# Sapflux-Basic_AltB.net
KiCad netlist of a schematic drawn in EAGLE
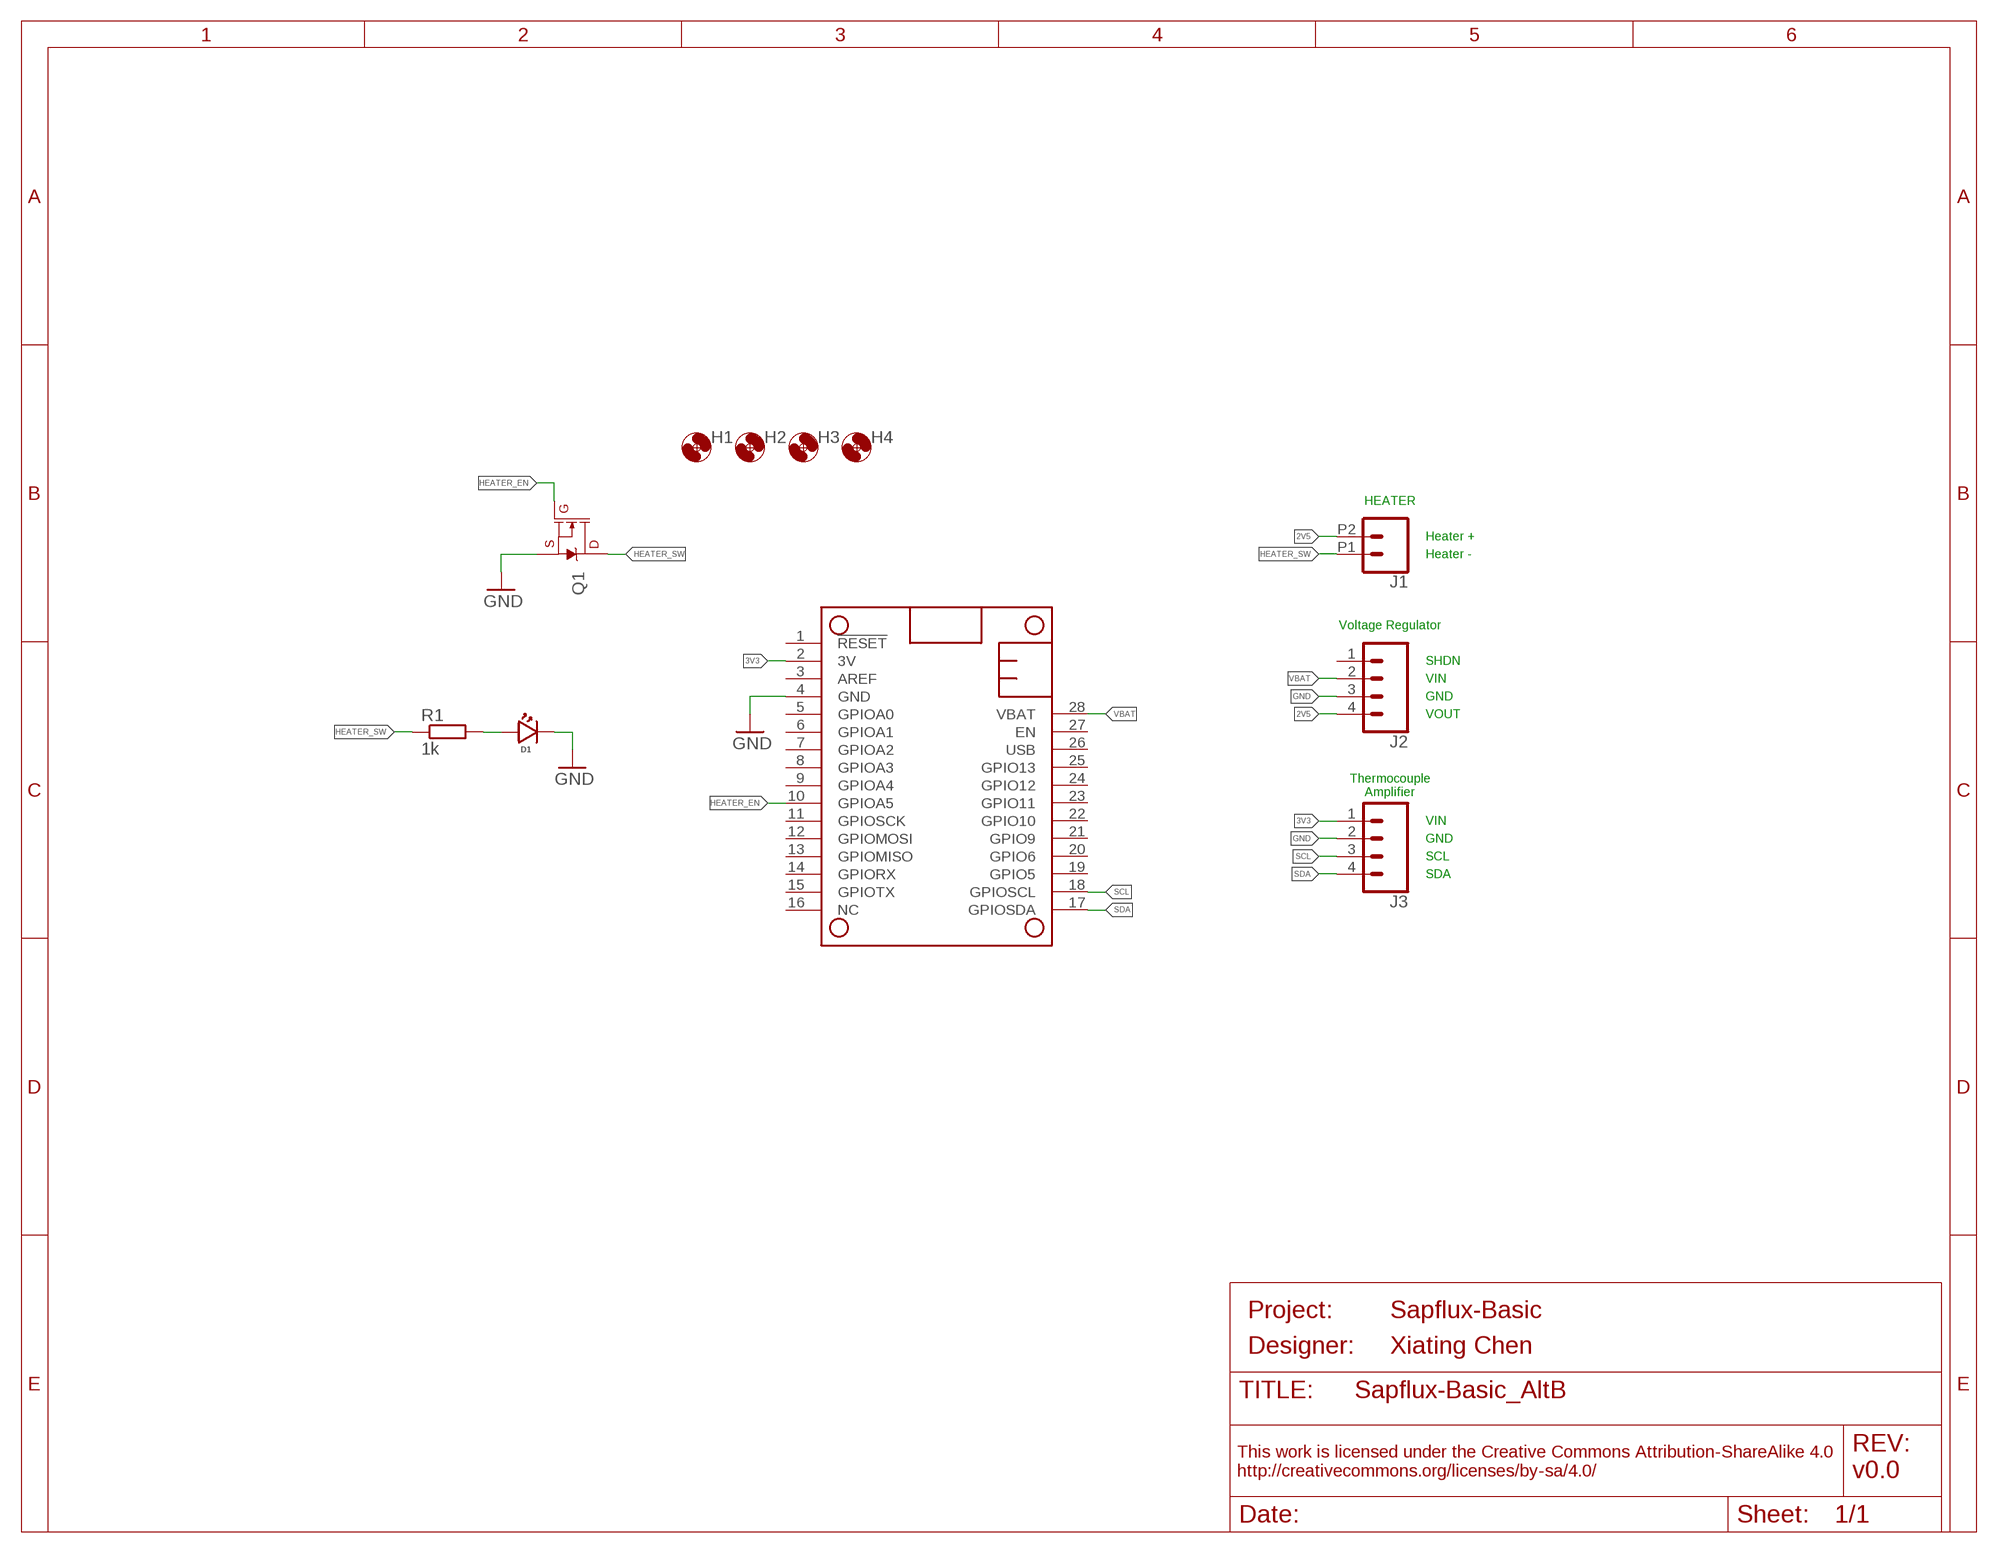
[diagram p0: schematic, sheet 1]

(export (version "E")
  (design (tool "Eeschema 10.0.6"))
  (components
    (comp (ref "D1")
      (value "LED3MM")
      (footprint "eagle-import:LED_3MM")
      (libsource (lib "eagle-import") (part "LED3MM"))
    )
    (comp (ref "H1")
      (value "MOUNTING_HOLE4_NP")
      (footprint "eagle-import:4_40")
      (fields (field (name "MPN") "DNP"))
      (libsource (lib "eagle-import") (part "MOUNTING_HOLE4_NP"))
    )
    (comp (ref "H2")
      (value "MOUNTING_HOLE4_NP")
      (footprint "eagle-import:4_40")
      (fields (field (name "MPN") "DNP"))
      (libsource (lib "eagle-import") (part "MOUNTING_HOLE4_NP"))
    )
    (comp (ref "H3")
      (value "MOUNTING_HOLE4_NP")
      (footprint "eagle-import:4_40")
      (fields (field (name "MPN") "DNP"))
      (libsource (lib "eagle-import") (part "MOUNTING_HOLE4_NP"))
    )
    (comp (ref "H4")
      (value "MOUNTING_HOLE4_NP")
      (footprint "eagle-import:4_40")
      (fields (field (name "MPN") "DNP"))
      (libsource (lib "eagle-import") (part "MOUNTING_HOLE4_NP"))
    )
    (comp (ref "J1")
      (value "CONN_2")
      (footprint "eagle-import:1X02_2.54_SCREWTERM_ROUND")
      (fields (field (name "MF") "OnShore") (field (name "MPN") "OSTVN02A150"))
      (libsource (lib "eagle-import") (part "CONN_022.54_SCREW_ROUND"))
    )
    (comp (ref "J2")
      (value "CONN_42.54")
      (footprint "eagle-import:1X04")
      (fields (field (name "MF") "Adam Tech") (field (name "MPN") "PH1-04-UA"))
      (libsource (lib "eagle-import") (part "CONN_42.54"))
    )
    (comp (ref "J3")
      (value "CONN_42.54")
      (footprint "eagle-import:1X04")
      (fields (field (name "MF") "Adam Tech") (field (name "MPN") "PH1-04-UA"))
      (libsource (lib "eagle-import") (part "CONN_42.54"))
    )
    (comp (ref "MS1")
      (value "FEATHERWINGLAYOUT")
      (footprint "eagle-import:FEATHERWING_MIN")
      (libsource (lib "eagle-import") (part "FEATHERWINGLAYOUT"))
    )
    (comp (ref "Q1")
      (value "60V/32A/35mΩ")
      (footprint "eagle-import:TO220V")
      (fields (field (name "MF") "Infineon") (field (name "MPN") "IRLB8721PBF"))
      (libsource (lib "eagle-import") (part "MOSFET-NCH-FQP30N06L"))
    )
    (comp (ref "R1")
      (value "1k")
      (footprint "eagle-import:0204_7")
      (libsource (lib "eagle-import") (part "R-EU_0204/7"))
    )
  )
  (nets
    (net (code "1") (name "/USB") (class "Default")
      (node (ref "MS1") (pin "26") (pinfunction "USB_26") (pintype "power_in"))
    )
    (net (code "2") (name "2V5") (class "Default")
      (node (ref "J1") (pin "P2") (pinfunction "2_P2") (pintype "passive"))
      (node (ref "J2") (pin "4") (pinfunction "4_4") (pintype "passive"))
    )
    (net (code "3") (name "3V3") (class "Default")
      (node (ref "J3") (pin "1") (pinfunction "1_1") (pintype "passive"))
      (node (ref "MS1") (pin "2") (pinfunction "3V_2") (pintype "power_in"))
    )
    (net (code "4") (name "GND") (class "Default")
      (node (ref "D1") (pin "2") (pinfunction "CATHODE_2") (pintype "power_in"))
      (node (ref "J2") (pin "3") (pinfunction "3_3") (pintype "passive"))
      (node (ref "J3") (pin "2") (pinfunction "2_2") (pintype "passive"))
      (node (ref "MS1") (pin "4") (pinfunction "GND_4") (pintype "power_in"))
      (node (ref "Q1") (pin "3") (pinfunction "S_3") (pintype "bidirectional"))
    )
    (net (code "5") (name "HEATER_EN") (class "Default")
      (node (ref "MS1") (pin "10") (pinfunction "GPIOA5_10") (pintype "bidirectional"))
      (node (ref "Q1") (pin "1") (pinfunction "G_1") (pintype "bidirectional"))
    )
    (net (code "6") (name "HEATER_SW") (class "Default")
      (node (ref "J1") (pin "P1") (pinfunction "1_P1") (pintype "passive"))
      (node (ref "Q1") (pin "2") (pinfunction "D_2") (pintype "bidirectional"))
      (node (ref "R1") (pin "1") (pinfunction "1_1") (pintype "passive"))
    )
    (net (code "7") (name "Net-(D1-ANODE)") (class "Default")
      (node (ref "D1") (pin "1") (pinfunction "ANODE_1") (pintype "power_in"))
      (node (ref "R1") (pin "2") (pinfunction "2_2") (pintype "passive"))
    )
    (net (code "8") (name "SCL") (class "Default")
      (node (ref "J3") (pin "3") (pinfunction "3_3") (pintype "passive"))
      (node (ref "MS1") (pin "18") (pinfunction "GPIOSCL_18") (pintype "bidirectional"))
    )
    (net (code "9") (name "SDA") (class "Default")
      (node (ref "J3") (pin "4") (pinfunction "4_4") (pintype "passive"))
      (node (ref "MS1") (pin "17") (pinfunction "GPIOSDA_17") (pintype "bidirectional"))
    )
    (net (code "10") (name "VBAT") (class "Default")
      (node (ref "J2") (pin "2") (pinfunction "2_2") (pintype "passive"))
      (node (ref "MS1") (pin "28") (pinfunction "VBAT_28") (pintype "power_in"))
    )
    (net (code "11") (name "unconnected-(J2-Pad1)") (class "Default")
      (node (ref "J2") (pin "1") (pinfunction "1_1") (pintype "passive"))
    )
    (net (code "12") (name "unconnected-(MS1-AREF-Pad3)") (class "Default")
      (node (ref "MS1") (pin "3") (pinfunction "AREF_3") (pintype "passive"))
    )
    (net (code "13") (name "unconnected-(MS1-EN-Pad27)") (class "Default")
      (node (ref "MS1") (pin "27") (pinfunction "EN_27") (pintype "passive"))
    )
    (net (code "14") (name "unconnected-(MS1-GPIO5-Pad19)") (class "Default")
      (node (ref "MS1") (pin "19") (pinfunction "GPIO5_19") (pintype "bidirectional"))
    )
    (net (code "15") (name "unconnected-(MS1-GPIO6-Pad20)") (class "Default")
      (node (ref "MS1") (pin "20") (pinfunction "GPIO6_20") (pintype "bidirectional"))
    )
    (net (code "16") (name "unconnected-(MS1-GPIO9-Pad21)") (class "Default")
      (node (ref "MS1") (pin "21") (pinfunction "GPIO9_21") (pintype "bidirectional"))
    )
    (net (code "17") (name "unconnected-(MS1-GPIO10-Pad22)") (class "Default")
      (node (ref "MS1") (pin "22") (pinfunction "GPIO10_22") (pintype "bidirectional"))
    )
    (net (code "18") (name "unconnected-(MS1-GPIO11-Pad23)") (class "Default")
      (node (ref "MS1") (pin "23") (pinfunction "GPIO11_23") (pintype "bidirectional"))
    )
    (net (code "19") (name "unconnected-(MS1-GPIO12-Pad24)") (class "Default")
      (node (ref "MS1") (pin "24") (pinfunction "GPIO12_24") (pintype "bidirectional"))
    )
    (net (code "20") (name "unconnected-(MS1-GPIO13-Pad25)") (class "Default")
      (node (ref "MS1") (pin "25") (pinfunction "GPIO13_25") (pintype "bidirectional"))
    )
    (net (code "21") (name "unconnected-(MS1-GPIOA0-Pad5)") (class "Default")
      (node (ref "MS1") (pin "5") (pinfunction "GPIOA0_5") (pintype "bidirectional"))
    )
    (net (code "22") (name "unconnected-(MS1-GPIOA1-Pad6)") (class "Default")
      (node (ref "MS1") (pin "6") (pinfunction "GPIOA1_6") (pintype "bidirectional"))
    )
    (net (code "23") (name "unconnected-(MS1-GPIOA2-Pad7)") (class "Default")
      (node (ref "MS1") (pin "7") (pinfunction "GPIOA2_7") (pintype "bidirectional"))
    )
    (net (code "24") (name "unconnected-(MS1-GPIOA3-Pad8)") (class "Default")
      (node (ref "MS1") (pin "8") (pinfunction "GPIOA3_8") (pintype "bidirectional"))
    )
    (net (code "25") (name "unconnected-(MS1-GPIOA4-Pad9)") (class "Default")
      (node (ref "MS1") (pin "9") (pinfunction "GPIOA4_9") (pintype "bidirectional"))
    )
    (net (code "26") (name "unconnected-(MS1-GPIOMISO-Pad13)") (class "Default")
      (node (ref "MS1") (pin "13") (pinfunction "GPIOMISO_13") (pintype "bidirectional"))
    )
    (net (code "27") (name "unconnected-(MS1-GPIOMOSI-Pad12)") (class "Default")
      (node (ref "MS1") (pin "12") (pinfunction "GPIOMOSI_12") (pintype "bidirectional"))
    )
    (net (code "28") (name "unconnected-(MS1-GPIORX-Pad14)") (class "Default")
      (node (ref "MS1") (pin "14") (pinfunction "GPIORX_14") (pintype "bidirectional"))
    )
    (net (code "29") (name "unconnected-(MS1-GPIOSCK-Pad11)") (class "Default")
      (node (ref "MS1") (pin "11") (pinfunction "GPIOSCK_11") (pintype "bidirectional"))
    )
    (net (code "30") (name "unconnected-(MS1-GPIOTX-Pad15)") (class "Default")
      (node (ref "MS1") (pin "15") (pinfunction "GPIOTX_15") (pintype "bidirectional"))
    )
    (net (code "31") (name "unconnected-(MS1-NC-Pad16)") (class "Default")
      (node (ref "MS1") (pin "16") (pinfunction "NC_16") (pintype "passive"))
    )
    (net (code "32") (name "unconnected-(MS1-~{RESET}-Pad1)") (class "Default")
      (node (ref "MS1") (pin "1") (pinfunction "~{RESET}_1") (pintype "input"))
    )
  )
)
